# schematicDoc.net
KiCad netlist of a schematic drawn in Altium Designer
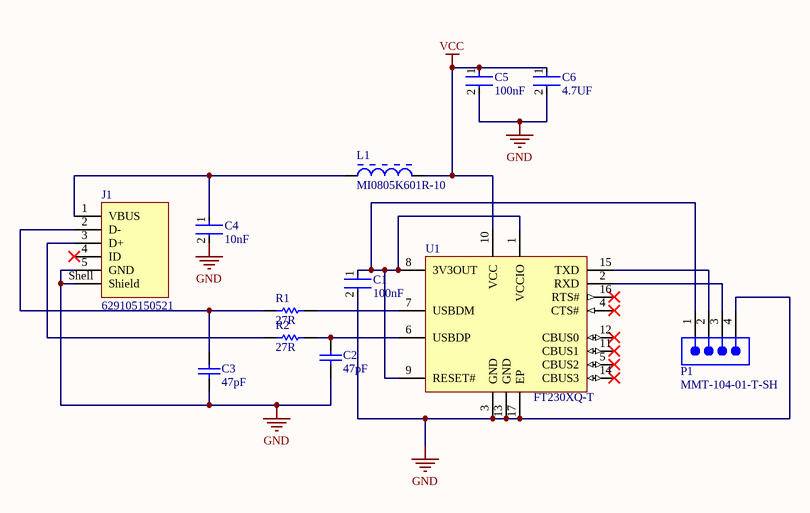
[diagram p0: schematicDoc.SchDoc]

(export (version "E")
  (design (tool "Eeschema 10.0.6"))
  (components
    (comp (ref "C1")
      (value "100nF")
      (footprint "FP-GRT31C-0_2-IPC_B")
      (description "Multi-Layer Ceramic Capacitor 100nF 25V C0G ±1% 1206 Emboss T/R")
      (libsource (lib "Altium Content Vault") (part "02cd4be3c70576c341d710602a673aa"))
    )
    (comp (ref "C2")
      (value "47pF")
      (footprint "CAPC1608X87X35NL15T15")
      (description "CAP CER 47PF 50V C0G/NP0 0603")
      (fields (field (name "PART NUMBER") "C0603X470J5GACTU") (field (name "MANUFACTURER") "Kemet"))
      (libsource (lib "Altium Content Vault") (part "CAP"))
    )
    (comp (ref "C3")
      (value "47pF")
      (footprint "CAPC1608X87X35NL15T15")
      (description "CAP CER 47PF 50V C0G/NP0 0603")
      (fields (field (name "PART NUMBER") "C0603X470J5GACTU") (field (name "MANUFACTURER") "Kemet"))
      (libsource (lib "Altium Content Vault") (part "CAP"))
    )
    (comp (ref "C4")
      (value "10nF")
      (footprint "FP-C0402-BB-MFG")
      (description "C0402 10 nF X7R 10.00% 16 V")
      (fields
        (field (name "TOLERANCE") "0.1")
        (field (name "OCTOPART") "https://octopart.com/c0402c103k4rac-kemet-1325399")
      )
      (libsource (lib "Altium Content Vault") (part "b4654b650e69147ec39a6b967a45e02"))
    )
    (comp (ref "C5")
      (value "100nF")
      (footprint "FP-GRT31C-0_2-IPC_B")
      (description "Multi-Layer Ceramic Capacitor 100nF 25V C0G ±1% 1206 Emboss T/R")
      (libsource (lib "Altium Content Vault") (part "02cd4be3c70576c341d710602a673aa"))
    )
    (comp (ref "C6")
      (value "4.7UF")
      (footprint "FP-CL21-IPC_A")
      (description "CL21 Series 0805 4.7uF 16V ±10% Tolerance X7R Multilayer Ceramic Chip Capacitor")
      (fields (field (name "TOLERANCE") "10%"))
      (libsource (lib "Altium Content Vault") (part "b4654b650e69147ec39a6b967a45e02"))
    )
    (comp (ref "J1")
      (value "629105150521")
      (footprint "629105150521")
      (description "USB Connector, 5 Contact(s), Female, Right Angle, Surface Mount Terminal, Locking")
      (libsource (lib "Altium Content Vault") (part "Micro USB 2.0_Type B_Receptacle_1 Port"))
    )
    (comp (ref "L1")
      (value "MI0805K601R-10")
      (footprint "LIRD-MI0805K601R-10-2_V")
      (fields (field (name "MANUFACTURER") "Laird"))
      (libsource (lib "Altium Content Vault") (part "IND-FB-2"))
    )
    (comp (ref "P1")
      (value "MMT-104-01-T-SH")
      (footprint "SMTC-MMT-104-01-X-SH")
      (description "Horizontal Surface Mount Header, -55 to 105 degC, 2 mm Pitch, 4-Pin, Male, RoHS")
      (fields (field (name "MANUFACTURER") "Samtec"))
      (libsource (lib "Altium Content Vault") (part "SMTC-MMT-104-X-X-SH"))
    )
    (comp (ref "R1")
      (value "27R")
      (footprint "RESC1005X40X25NL05T10")
      (description "27 Ohms ±5% 0.063W, 1/16W Chip Resistor 0402 (1005 Metric) Moisture Resistant Thick Film")
      (fields (field (name "MANUFACTURER") "Yageo") (field (name "PART NUMBER") "RC0402JR-1327RL"))
      (libsource (lib "Altium Content Vault") (part "RES"))
    )
    (comp (ref "R2")
      (value "27R")
      (footprint "RESC1005X40X25NL05T10")
      (description "27 Ohms ±5% 0.063W, 1/16W Chip Resistor 0402 (1005 Metric) Moisture Resistant Thick Film")
      (fields (field (name "MANUFACTURER") "Yageo") (field (name "PART NUMBER") "RC0402JR-1327RL"))
      (libsource (lib "Altium Content Vault") (part "RES"))
    )
    (comp (ref "U1")
      (value "FT230XQ-T")
      (footprint "QFN-16_M")
      (fields (field (name "MANUFACTURER") "FTDI"))
      (libsource (lib "Altium Content Vault") (part "COM-USB-FT230XQ-SQ17"))
    )
  )
  (nets
    (net (code "1") (name "GND") (class "Default")
      (node (ref "C1") (pin "2") (pinfunction "2_2") (pintype "passive"))
      (node (ref "C2") (pin "1") (pinfunction "1_1") (pintype "passive"))
      (node (ref "C3") (pin "1") (pinfunction "1_1") (pintype "passive"))
      (node (ref "C4") (pin "2") (pinfunction "2_2") (pintype "passive"))
      (node (ref "C5") (pin "2") (pinfunction "2_2") (pintype "passive"))
      (node (ref "C6") (pin "2") (pinfunction "2_2") (pintype "passive"))
      (node (ref "J1") (pin "5") (pinfunction "GND_5") (pintype "passive"))
      (node (ref "J1") (pin "Shell") (pinfunction "Shield_Shell") (pintype "passive"))
      (node (ref "P1") (pin "4") (pinfunction "4_4") (pintype "passive"))
      (node (ref "U1") (pin "13") (pinfunction "GND_13") (pintype "power_in"))
      (node (ref "U1") (pin "17") (pinfunction "EP_17") (pintype "power_in"))
      (node (ref "U1") (pin "3") (pinfunction "GND_3") (pintype "power_in"))
    )
    (net (code "2") (name "Net-(J1-D+)") (class "Default")
      (node (ref "J1") (pin "3") (pinfunction "D+_3") (pintype "passive"))
      (node (ref "R2") (pin "1") (pinfunction "1_1") (pintype "passive"))
    )
    (net (code "3") (name "Net-(J1-D-)") (class "Default")
      (node (ref "C3") (pin "2") (pinfunction "2_2") (pintype "passive"))
      (node (ref "J1") (pin "2") (pinfunction "D-_2") (pintype "passive"))
      (node (ref "R1") (pin "1") (pinfunction "1_1") (pintype "passive"))
    )
    (net (code "4") (name "Net-(J1-VBUS)") (class "Default")
      (node (ref "C4") (pin "1") (pinfunction "1_1") (pintype "passive"))
      (node (ref "J1") (pin "1") (pinfunction "VBUS_1") (pintype "passive"))
      (node (ref "L1") (pin "1") (pinfunction "1_1") (pintype "passive"))
    )
    (net (code "5") (name "Net-(U1-3V3OUT)") (class "Default")
      (node (ref "C1") (pin "1") (pinfunction "1_1") (pintype "passive"))
      (node (ref "P1") (pin "1") (pinfunction "1_1") (pintype "passive"))
      (node (ref "U1") (pin "1") (pinfunction "VCCIO_1") (pintype "power_in"))
      (node (ref "U1") (pin "8") (pinfunction "3V3OUT_8") (pintype "power_in"))
      (node (ref "U1") (pin "9") (pinfunction "RESET#_9") (pintype "passive"))
    )
    (net (code "6") (name "Net-(U1-RXD)") (class "Default")
      (node (ref "P1") (pin "3") (pinfunction "3_3") (pintype "passive"))
      (node (ref "U1") (pin "2") (pinfunction "RXD_2") (pintype "passive"))
    )
    (net (code "7") (name "Net-(U1-TXD)") (class "Default")
      (node (ref "P1") (pin "2") (pinfunction "2_2") (pintype "passive"))
      (node (ref "U1") (pin "15") (pinfunction "TXD_15") (pintype "passive"))
    )
    (net (code "8") (name "Net-(U1-USBDM)") (class "Default")
      (node (ref "R1") (pin "2") (pinfunction "2_2") (pintype "passive"))
      (node (ref "U1") (pin "7") (pinfunction "USBDM_7") (pintype "passive"))
    )
    (net (code "9") (name "Net-(U1-USBDP)") (class "Default")
      (node (ref "C2") (pin "2") (pinfunction "2_2") (pintype "passive"))
      (node (ref "R2") (pin "2") (pinfunction "2_2") (pintype "passive"))
      (node (ref "U1") (pin "6") (pinfunction "USBDP_6") (pintype "passive"))
    )
    (net (code "10") (name "VCC") (class "Default")
      (node (ref "C5") (pin "1") (pinfunction "1_1") (pintype "passive"))
      (node (ref "C6") (pin "1") (pinfunction "1_1") (pintype "passive"))
      (node (ref "L1") (pin "2") (pinfunction "2_2") (pintype "passive"))
      (node (ref "U1") (pin "10") (pinfunction "VCC_10") (pintype "power_in"))
    )
    (net (code "11") (name "unconnected-(J1-ID-Pad4)") (class "Default")
      (node (ref "J1") (pin "4") (pinfunction "ID_4") (pintype "passive+no_connect"))
    )
    (net (code "12") (name "unconnected-(U1-CBUS0-Pad12)") (class "Default")
      (node (ref "U1") (pin "12") (pinfunction "CBUS0_12") (pintype "bidirectional+no_connect"))
    )
    (net (code "13") (name "unconnected-(U1-CBUS1-Pad11)") (class "Default")
      (node (ref "U1") (pin "11") (pinfunction "CBUS1_11") (pintype "bidirectional+no_connect"))
    )
    (net (code "14") (name "unconnected-(U1-CBUS2-Pad5)") (class "Default")
      (node (ref "U1") (pin "5") (pinfunction "CBUS2_5") (pintype "bidirectional+no_connect"))
    )
    (net (code "15") (name "unconnected-(U1-CBUS3-Pad14)") (class "Default")
      (node (ref "U1") (pin "14") (pinfunction "CBUS3_14") (pintype "bidirectional+no_connect"))
    )
    (net (code "16") (name "unconnected-(U1-CTS#-Pad4)") (class "Default")
      (node (ref "U1") (pin "4") (pinfunction "CTS#_4") (pintype "input+no_connect"))
    )
    (net (code "17") (name "unconnected-(U1-RTS#-Pad16)") (class "Default")
      (node (ref "U1") (pin "16") (pinfunction "RTS#_16") (pintype "output+no_connect"))
    )
  )
)
